# AdControl.net
KiCad netlist of a schematic drawn in Altium Designer
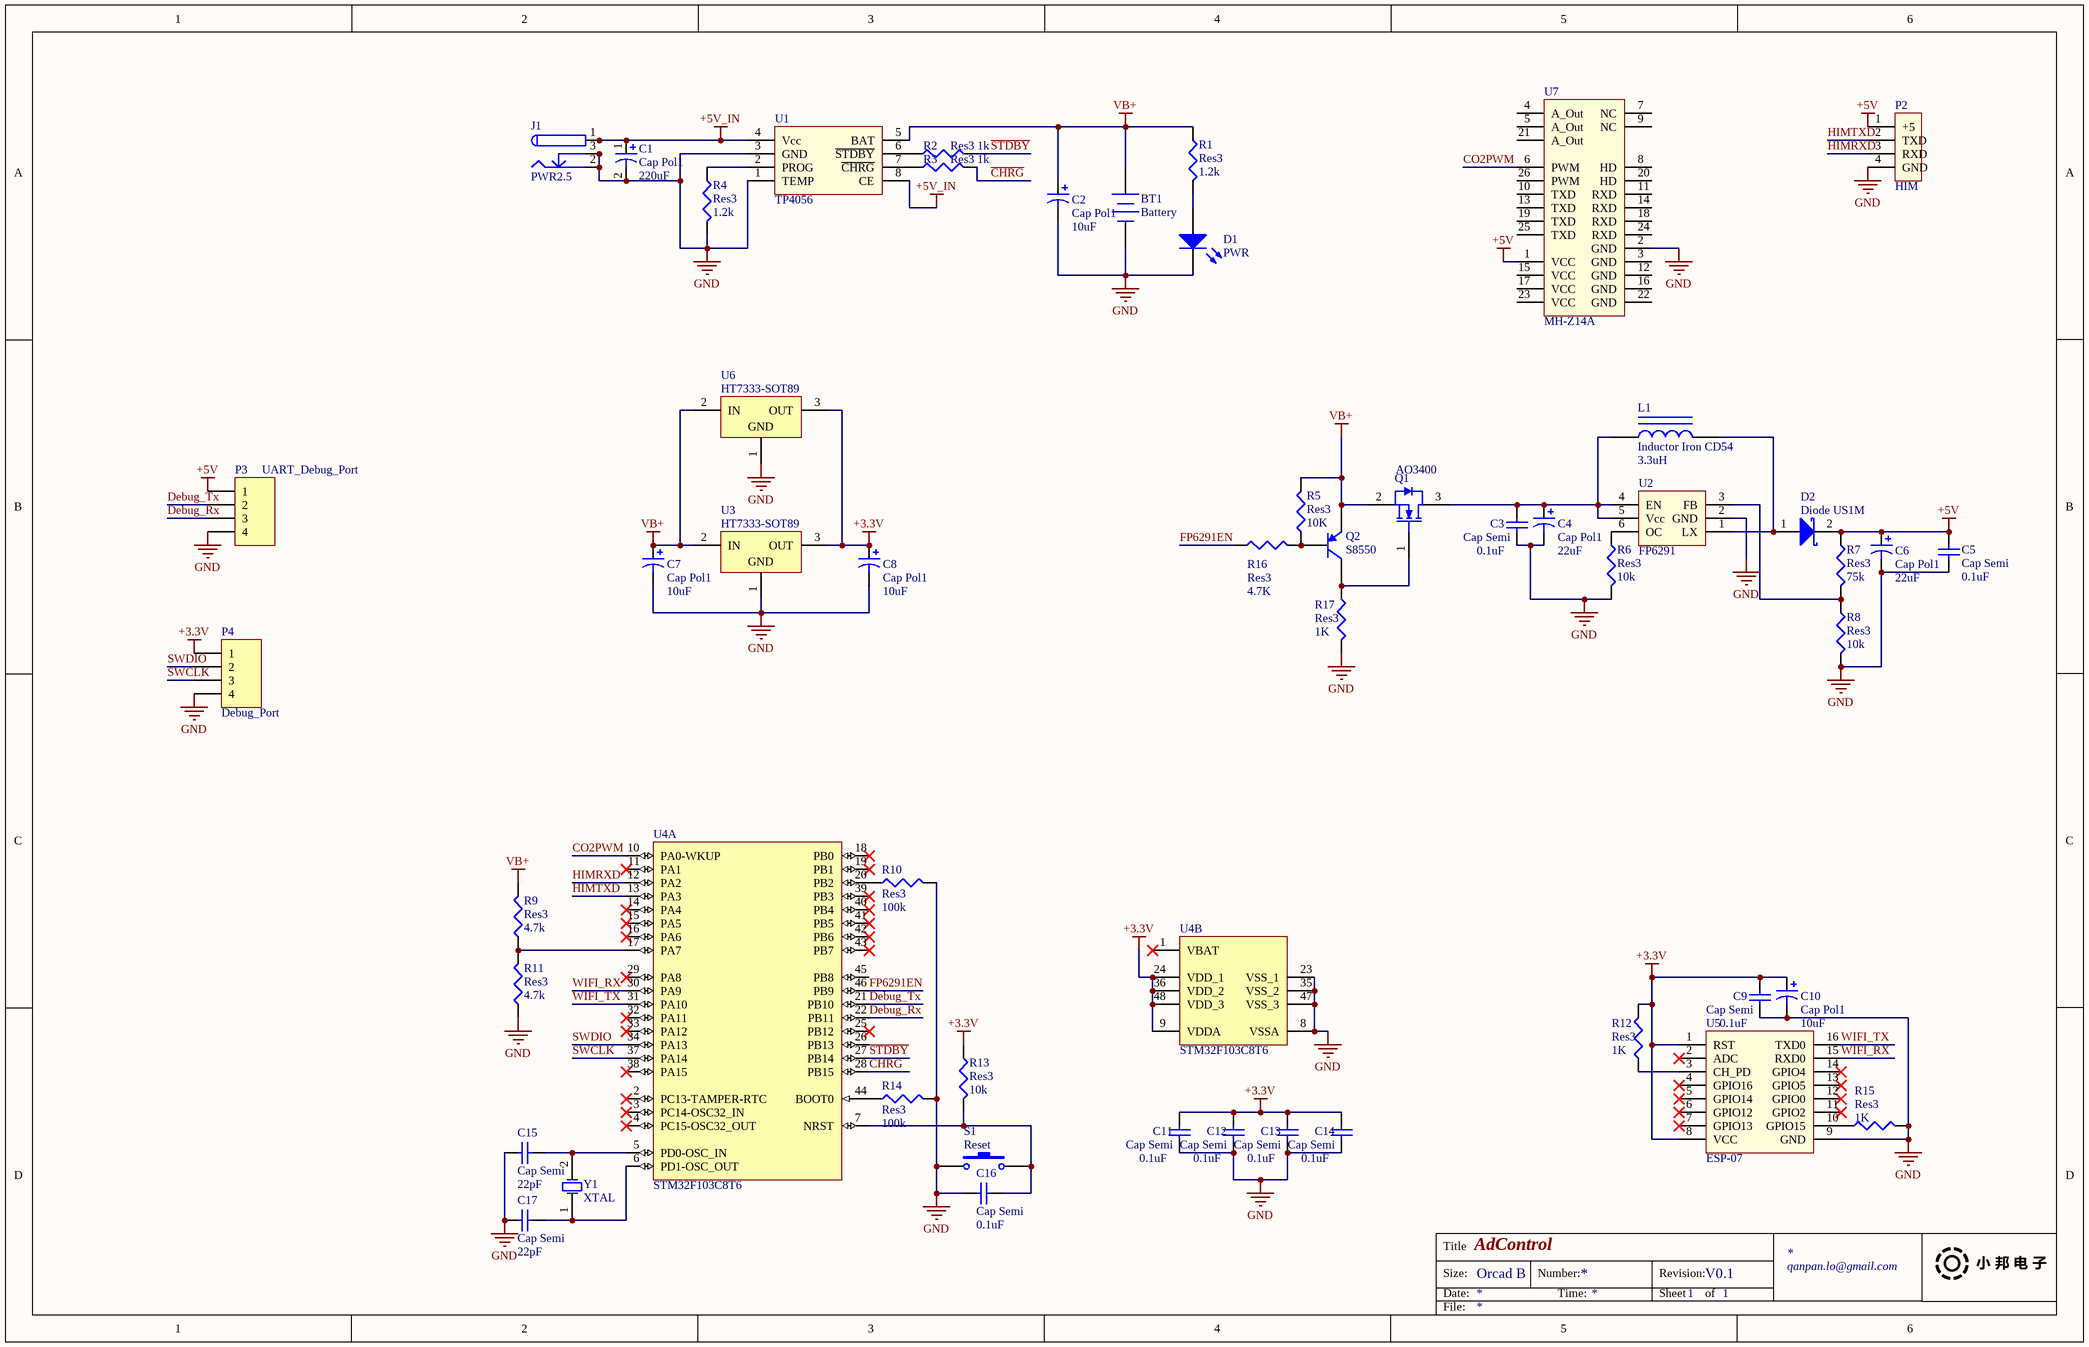
[diagram p0: AdControl.SchDoc]

(export (version "E")
  (design (tool "Eeschema 10.0.6"))
  (components
    (comp (ref "BT1")
      (value "Battery")
      (footprint "KF3.96_2P")
      (description "Multicell Battery")
      (fields (field (name "PUBLISHER") "Altium Limited"))
      (libsource (lib "Miscellaneous Devices") (part "Battery"))
    )
    (comp (ref "C1")
      (value "Cap Pol1")
      (footprint "CAP_6.3*5.4MM")
      (description "Polarized Capacitor (Radial)")
      (fields (field (name "ALTIUM_VALUE") "220uF") (field (name "PUBLISHER") "Altium Limited"))
      (libsource (lib "") (part "Cap Pol1_1"))
    )
    (comp (ref "C2")
      (value "Cap Pol1")
      (footprint "Cap_5*4mm")
      (description "Polarized Capacitor (Radial)")
      (fields (field (name "ALTIUM_VALUE") "10uF") (field (name "PUBLISHER") "Altium Limited"))
      (libsource (lib "Miscellaneous Devices") (part "Cap Pol1"))
    )
    (comp (ref "C3")
      (value "Cap Semi")
      (footprint "6-0805_N")
      (description "Capacitor (Semiconductor SIM Model)")
      (fields (field (name "ALTIUM_VALUE") "0.1uF") (field (name "PUBLISHER") "Altium Limited"))
      (libsource (lib "Miscellaneous Devices") (part "Cap Semi"))
    )
    (comp (ref "C4")
      (value "Cap Pol1")
      (footprint "Cap_5*4mm")
      (description "Polarized Capacitor (Radial)")
      (fields (field (name "ALTIUM_VALUE") "22uF") (field (name "PUBLISHER") "Altium Limited"))
      (libsource (lib "Miscellaneous Devices") (part "Cap Pol1"))
    )
    (comp (ref "C5")
      (value "Cap Semi")
      (footprint "6-0805_N")
      (description "Capacitor (Semiconductor SIM Model)")
      (fields (field (name "ALTIUM_VALUE") "0.1uF") (field (name "PUBLISHER") "Altium Limited"))
      (libsource (lib "Miscellaneous Devices") (part "Cap Semi"))
    )
    (comp (ref "C6")
      (value "Cap Pol1")
      (footprint "Cap_5*4mm")
      (description "Polarized Capacitor (Radial)")
      (fields (field (name "ALTIUM_VALUE") "22uF") (field (name "PUBLISHER") "Altium Limited"))
      (libsource (lib "Miscellaneous Devices") (part "Cap Pol1"))
    )
    (comp (ref "C7")
      (value "Cap Pol1")
      (footprint "Cap_5*4mm")
      (description "Polarized Capacitor (Radial)")
      (fields (field (name "ALTIUM_VALUE") "10uF") (field (name "PUBLISHER") "Altium Limited"))
      (libsource (lib "Miscellaneous Devices") (part "Cap Pol1"))
    )
    (comp (ref "C8")
      (value "Cap Pol1")
      (footprint "Cap_5*4mm")
      (description "Polarized Capacitor (Radial)")
      (fields (field (name "ALTIUM_VALUE") "10uF") (field (name "PUBLISHER") "Altium Limited"))
      (libsource (lib "Miscellaneous Devices") (part "Cap Pol1"))
    )
    (comp (ref "C9")
      (value "Cap Semi")
      (footprint "6-0805_N")
      (description "Capacitor (Semiconductor SIM Model)")
      (fields (field (name "ALTIUM_VALUE") "0.1uF") (field (name "PUBLISHER") "Altium Limited"))
      (libsource (lib "Miscellaneous Devices") (part "Cap Semi"))
    )
    (comp (ref "C10")
      (value "Cap Pol1")
      (footprint "Cap_5*4mm")
      (description "Polarized Capacitor (Radial)")
      (fields (field (name "ALTIUM_VALUE") "10uF") (field (name "PUBLISHER") "Altium Limited"))
      (libsource (lib "Miscellaneous Devices") (part "Cap Pol1"))
    )
    (comp (ref "C11")
      (value "Cap Semi")
      (footprint "6-0805_N")
      (description "Capacitor (Semiconductor SIM Model)")
      (fields (field (name "ALTIUM_VALUE") "0.1uF") (field (name "PUBLISHER") "Altium Limited"))
      (libsource (lib "Miscellaneous Devices") (part "Cap Semi"))
    )
    (comp (ref "C12")
      (value "Cap Semi")
      (footprint "6-0805_N")
      (description "Capacitor (Semiconductor SIM Model)")
      (fields (field (name "ALTIUM_VALUE") "0.1uF") (field (name "PUBLISHER") "Altium Limited"))
      (libsource (lib "Miscellaneous Devices") (part "Cap Semi"))
    )
    (comp (ref "C13")
      (value "Cap Semi")
      (footprint "6-0805_N")
      (description "Capacitor (Semiconductor SIM Model)")
      (fields (field (name "ALTIUM_VALUE") "0.1uF") (field (name "PUBLISHER") "Altium Limited"))
      (libsource (lib "Miscellaneous Devices") (part "Cap Semi"))
    )
    (comp (ref "C14")
      (value "Cap Semi")
      (footprint "6-0805_N")
      (description "Capacitor (Semiconductor SIM Model)")
      (fields (field (name "ALTIUM_VALUE") "0.1uF") (field (name "PUBLISHER") "Altium Limited"))
      (libsource (lib "Miscellaneous Devices") (part "Cap Semi"))
    )
    (comp (ref "C15")
      (value "Cap Semi")
      (footprint "6-0805_N")
      (description "Capacitor (Semiconductor SIM Model)")
      (fields (field (name "ALTIUM_VALUE") "22pF") (field (name "PUBLISHER") "Altium Limited"))
      (libsource (lib "Miscellaneous Devices") (part "Cap Semi"))
    )
    (comp (ref "C16")
      (value "Cap Semi")
      (footprint "6-0805_N")
      (description "Capacitor (Semiconductor SIM Model)")
      (fields (field (name "ALTIUM_VALUE") "0.1uF") (field (name "PUBLISHER") "Altium Limited"))
      (libsource (lib "Miscellaneous Devices") (part "Cap Semi"))
    )
    (comp (ref "C17")
      (value "Cap Semi")
      (footprint "6-0805_N")
      (description "Capacitor (Semiconductor SIM Model)")
      (fields (field (name "ALTIUM_VALUE") "22pF") (field (name "PUBLISHER") "Altium Limited"))
      (libsource (lib "Miscellaneous Devices") (part "Cap Semi"))
    )
    (comp (ref "D1")
      (value "PWR")
      (footprint "6-0805_N")
      (description "Typical INFRARED GaAs LED")
      (fields (field (name "PUBLISHER") "Altium Limited"))
      (libsource (lib "Miscellaneous Devices") (part "LED0"))
    )
    (comp (ref "D2")
      (value "Diode US1M")
      (footprint "US1M")
      (description "Silicon RF Schottky Diode for Mixer Applications in the VHF/UHF Range")
      (fields (field (name "PUBLISHER") "Altium Limited"))
      (libsource (lib "Miscellaneous Devices") (part "Diode BAT17"))
    )
    (comp (ref "J1")
      (value "PWR2.5")
      (footprint "KLD-3.5-1.3mm")
      (description "Low Voltage Power Supply Connector")
      (fields (field (name "PUBLISHER") "Altium Limited"))
      (libsource (lib "Miscellaneous Connectors") (part "PWR2.5"))
    )
    (comp (ref "L1")
      (value "Inductor Iron CD54")
      (footprint "CD54_Inductor")
      (description "Magnetic-Core Inductor")
      (fields (field (name "ALTIUM_VALUE") "3.3uH") (field (name "PUBLISHER") "Altium Limited"))
      (libsource (lib "Miscellaneous Devices") (part "Inductor Iron"))
    )
    (comp (ref "P2") (value "HIM") (footprint "XH2.54-4P") (libsource (lib "XH2.54") (part "XH2.54-4P")))
    (comp (ref "P3")
      (value "UART_Debug_Port")
      (footprint "HDR1X4")
      (description "Header, 4-Pin")
      (fields (field (name "PUBLISHER") "Altium Limited"))
      (libsource (lib "Miscellaneous Connectors") (part "Header 4"))
    )
    (comp (ref "P4")
      (value "Debug_Port")
      (footprint "HDR1X4")
      (description "Header, 4-Pin")
      (fields (field (name "PUBLISHER") "Altium Limited"))
      (libsource (lib "Miscellaneous Connectors") (part "Header 4"))
    )
    (comp (ref "Q1")
      (value "AO3400")
      (footprint "AO-SOT23-3_V")
      (description "N-channel Enhancement Mode Field-Effect Transistor; 5.8A/30V")
      (fields (field (name "MANUFACTURER") "Alpha and Omega"))
      (libsource (lib "Altium Content Vault") (part "AO-NEMOS-G1S2D3-3"))
    )
    (comp (ref "Q2")
      (value "S8550")
      (footprint "SOT-23B_L")
      (description "PNP Bipolar Transistor")
      (fields (field (name "PUBLISHER") "Altium Limited"))
      (libsource (lib "Miscellaneous Devices") (part "PNP"))
    )
    (comp (ref "R1")
      (value "Res3")
      (footprint "6-0805_N")
      (description "Resistor")
      (fields (field (name "ALTIUM_VALUE") "1.2k") (field (name "PUBLISHER") "Altium Limited"))
      (libsource (lib "Miscellaneous Devices") (part "Res3"))
    )
    (comp (ref "R2")
      (value "Res3")
      (footprint "6-0805_N")
      (description "Resistor")
      (fields (field (name "ALTIUM_VALUE") "1k") (field (name "PUBLISHER") "Altium Limited"))
      (libsource (lib "Miscellaneous Devices") (part "Res3"))
    )
    (comp (ref "R3")
      (value "Res3")
      (footprint "6-0805_N")
      (description "Resistor")
      (fields (field (name "ALTIUM_VALUE") "1k") (field (name "PUBLISHER") "Altium Limited"))
      (libsource (lib "Miscellaneous Devices") (part "Res3"))
    )
    (comp (ref "R4")
      (value "Res3")
      (footprint "6-0805_N")
      (description "Resistor")
      (fields (field (name "ALTIUM_VALUE") "1.2k") (field (name "PUBLISHER") "Altium Limited"))
      (libsource (lib "Miscellaneous Devices") (part "Res3"))
    )
    (comp (ref "R5")
      (value "Res3")
      (footprint "6-0805_N")
      (description "Resistor")
      (fields (field (name "ALTIUM_VALUE") "10K") (field (name "PUBLISHER") "Altium Limited"))
      (libsource (lib "Miscellaneous Devices") (part "Res3"))
    )
    (comp (ref "R6")
      (value "Res3")
      (footprint "6-0805_N")
      (description "Resistor")
      (fields (field (name "ALTIUM_VALUE") "10k") (field (name "PUBLISHER") "Altium Limited"))
      (libsource (lib "Miscellaneous Devices") (part "Res3"))
    )
    (comp (ref "R7")
      (value "Res3")
      (footprint "6-0805_N")
      (description "Resistor")
      (fields (field (name "ALTIUM_VALUE") "75k") (field (name "PUBLISHER") "Altium Limited"))
      (libsource (lib "Miscellaneous Devices") (part "Res3"))
    )
    (comp (ref "R8")
      (value "Res3")
      (footprint "6-0805_N")
      (description "Resistor")
      (fields (field (name "ALTIUM_VALUE") "10k") (field (name "PUBLISHER") "Altium Limited"))
      (libsource (lib "Miscellaneous Devices") (part "Res3"))
    )
    (comp (ref "R9")
      (value "Res3")
      (footprint "6-0805_N")
      (description "Resistor")
      (fields (field (name "ALTIUM_VALUE") "4.7k") (field (name "PUBLISHER") "Altium Limited"))
      (libsource (lib "Miscellaneous Devices") (part "Res3"))
    )
    (comp (ref "R10")
      (value "Res3")
      (footprint "6-0805_N")
      (description "Resistor")
      (fields (field (name "ALTIUM_VALUE") "100k") (field (name "PUBLISHER") "Altium Limited"))
      (libsource (lib "Miscellaneous Devices") (part "Res3"))
    )
    (comp (ref "R11")
      (value "Res3")
      (footprint "6-0805_N")
      (description "Resistor")
      (fields (field (name "ALTIUM_VALUE") "4.7k") (field (name "PUBLISHER") "Altium Limited"))
      (libsource (lib "Miscellaneous Devices") (part "Res3"))
    )
    (comp (ref "R12")
      (value "Res3")
      (footprint "6-0805_N")
      (description "Resistor")
      (fields (field (name "ALTIUM_VALUE") "1K") (field (name "PUBLISHER") "Altium Limited"))
      (libsource (lib "Miscellaneous Devices") (part "Res3"))
    )
    (comp (ref "R13")
      (value "Res3")
      (footprint "6-0805_N")
      (description "Resistor")
      (fields (field (name "ALTIUM_VALUE") "10k") (field (name "PUBLISHER") "Altium Limited"))
      (libsource (lib "Miscellaneous Devices") (part "Res3"))
    )
    (comp (ref "R14")
      (value "Res3")
      (footprint "6-0805_N")
      (description "Resistor")
      (fields (field (name "ALTIUM_VALUE") "100k") (field (name "PUBLISHER") "Altium Limited"))
      (libsource (lib "Miscellaneous Devices") (part "Res3"))
    )
    (comp (ref "R15")
      (value "Res3")
      (footprint "6-0805_N")
      (description "Resistor")
      (fields (field (name "ALTIUM_VALUE") "1K") (field (name "PUBLISHER") "Altium Limited"))
      (libsource (lib "Miscellaneous Devices") (part "Res3"))
    )
    (comp (ref "R16")
      (value "Res3")
      (footprint "6-0805_N")
      (description "Resistor")
      (fields (field (name "ALTIUM_VALUE") "4.7K") (field (name "PUBLISHER") "Altium Limited"))
      (libsource (lib "Miscellaneous Devices") (part "Res3"))
    )
    (comp (ref "R17")
      (value "Res3")
      (footprint "6-0805_N")
      (description "Resistor")
      (fields (field (name "ALTIUM_VALUE") "1K") (field (name "PUBLISHER") "Altium Limited"))
      (libsource (lib "Miscellaneous Devices") (part "Res3"))
    )
    (comp (ref "S1")
      (value "Reset")
      (footprint "SWP_PB_6.5mm")
      (description "Switch")
      (fields (field (name "PUBLISHER") "Altium Limited"))
      (libsource (lib "Miscellaneous Devices") (part "SW-PB"))
    )
    (comp (ref "U1")
      (value "TP4056")
      (footprint "Power_SOP8")
      (libsource (lib "Simon'Library") (part "TP4056"))
    )
    (comp (ref "U2")
      (value "FP6291")
      (footprint "SOT23-6L")
      (libsource (lib "Simon'Library") (part "FP6291"))
    )
    (comp (ref "U3")
      (value "HT7333-SOT89")
      (footprint "SOT89_N")
      (description "Low Power Consumption LDO, Output Voltage 3.3V, SOT89 Pkg")
      (libsource (lib "Altium Content Vault") (part "PM-REG-HT73XX-IL3"))
    )
    (comp (ref "U4")
      (value "STM32F103C8T6")
      (footprint "STM-LQFP48_L")
      (libsource (lib "Altium Content Vault") (part "MC-ARM-STM32F103X8_B-SQ48"))
    )
    (comp (ref "U5")
      (value "ESP-07")
      (footprint "ESP-07_Wifi")
      (libsource (lib "Simon'Library") (part "ESP-07_Wifi"))
    )
    (comp (ref "U6")
      (value "HT7333-SOT89")
      (footprint "SOT89_N")
      (description "Low Power Consumption LDO, Output Voltage 3.3V, SOT89 Pkg")
      (libsource (lib "Altium Content Vault") (part "PM-REG-HT73XX-IL3"))
    )
    (comp (ref "U7")
      (value "MH-Z14A")
      (footprint "MH-Z14A")
      (description "CO2 Detector")
      (libsource (lib "Simon'Library") (part "MH-Z14A"))
    )
    (comp (ref "Y1")
      (value "XTAL")
      (footprint "OSC_5032_2Pin")
      (description "Crystal Oscillator")
      (fields (field (name "PUBLISHER") "Altium Limited"))
      (libsource (lib "Miscellaneous Devices") (part "XTAL"))
    )
  )
  (nets
    (net (code "1") (name "+3.3V") (class "Default")
      (node (ref "C10") (pin "1") (pinfunction "1_1") (pintype "passive"))
      (node (ref "C11") (pin "1") (pinfunction "1_1") (pintype "passive"))
      (node (ref "C12") (pin "1") (pinfunction "1_1") (pintype "passive"))
      (node (ref "C13") (pin "1") (pinfunction "1_1") (pintype "passive"))
      (node (ref "C14") (pin "1") (pinfunction "1_1") (pintype "passive"))
      (node (ref "C8") (pin "1") (pinfunction "1_1") (pintype "passive"))
      (node (ref "C9") (pin "1") (pinfunction "1_1") (pintype "passive"))
      (node (ref "P4") (pin "1") (pinfunction "1_1") (pintype "passive"))
      (node (ref "R12") (pin "2") (pinfunction "2_2") (pintype "passive"))
      (node (ref "R13") (pin "1") (pinfunction "1_1") (pintype "passive"))
      (node (ref "U3") (pin "3") (pinfunction "OUT_3") (pintype "power_in"))
      (node (ref "U4") (pin "24") (pinfunction "VDD_1_24") (pintype "power_in"))
      (node (ref "U4") (pin "36") (pinfunction "VDD_2_36") (pintype "power_in"))
      (node (ref "U4") (pin "48") (pinfunction "VDD_3_48") (pintype "power_in"))
      (node (ref "U4") (pin "9") (pinfunction "VDDA_9") (pintype "power_in"))
      (node (ref "U5") (pin "1") (pinfunction "RST_1") (pintype "passive"))
      (node (ref "U5") (pin "8") (pinfunction "VCC_8") (pintype "passive"))
      (node (ref "U6") (pin "3") (pinfunction "OUT_3") (pintype "power_in"))
    )
    (net (code "2") (name "+5V") (class "Default")
      (node (ref "C5") (pin "1") (pinfunction "1_1") (pintype "passive"))
      (node (ref "C6") (pin "1") (pinfunction "1_1") (pintype "passive"))
      (node (ref "D2") (pin "2") (pinfunction "K_2") (pintype "passive"))
      (node (ref "P2") (pin "1") (pinfunction "+5_1") (pintype "passive"))
      (node (ref "P3") (pin "1") (pinfunction "1_1") (pintype "passive"))
      (node (ref "R7") (pin "1") (pinfunction "1_1") (pintype "passive"))
      (node (ref "U7") (pin "1") (pinfunction "VCC_1") (pintype "passive"))
    )
    (net (code "3") (name "+5V_IN") (class "Default")
      (node (ref "C1") (pin "1") (pinfunction "1_1") (pintype "passive"))
      (node (ref "J1") (pin "1") (pinfunction "1_1") (pintype "power_in"))
      (node (ref "J1") (pin "1A") (pinfunction "1A_1A") (pintype "power_in"))
      (node (ref "J1") (pin "1B") (pinfunction "1B_1B") (pintype "power_in"))
      (node (ref "U1") (pin "4") (pinfunction "Vcc_4") (pintype "passive"))
      (node (ref "U1") (pin "8") (pinfunction "CE_8") (pintype "passive"))
    )
    (net (code "4") (name "/CO2PWM") (class "Default")
      (node (ref "U4") (pin "10") (pinfunction "PA0-WKUP_10") (pintype "bidirectional"))
      (node (ref "U7") (pin "6") (pinfunction "PWM_6") (pintype "passive"))
    )
    (net (code "5") (name "/Debug_Rx") (class "Default")
      (node (ref "P3") (pin "3") (pinfunction "3_3") (pintype "passive"))
      (node (ref "U4") (pin "22") (pinfunction "PB11_22") (pintype "bidirectional"))
    )
    (net (code "6") (name "/Debug_Tx") (class "Default")
      (node (ref "P3") (pin "2") (pinfunction "2_2") (pintype "passive"))
      (node (ref "U4") (pin "21") (pinfunction "PB10_21") (pintype "bidirectional"))
    )
    (net (code "7") (name "/FP6291EN") (class "Default")
      (node (ref "R16") (pin "1") (pinfunction "1_1") (pintype "passive"))
      (node (ref "U4") (pin "46") (pinfunction "PB9_46") (pintype "bidirectional"))
    )
    (net (code "8") (name "/HIMRXD") (class "Default")
      (node (ref "P2") (pin "3") (pinfunction "RXD_3") (pintype "passive"))
      (node (ref "U4") (pin "12") (pinfunction "PA2_12") (pintype "bidirectional"))
    )
    (net (code "9") (name "/HIMTXD") (class "Default")
      (node (ref "P2") (pin "2") (pinfunction "TXD_2") (pintype "passive"))
      (node (ref "U4") (pin "13") (pinfunction "PA3_13") (pintype "bidirectional"))
    )
    (net (code "10") (name "/SWCLK") (class "Default")
      (node (ref "P4") (pin "3") (pinfunction "3_3") (pintype "passive"))
      (node (ref "U4") (pin "37") (pinfunction "PA14_37") (pintype "bidirectional"))
    )
    (net (code "11") (name "/SWDIO") (class "Default")
      (node (ref "P4") (pin "2") (pinfunction "2_2") (pintype "passive"))
      (node (ref "U4") (pin "34") (pinfunction "PA13_34") (pintype "bidirectional"))
    )
    (net (code "12") (name "/WIFI_RX") (class "Default")
      (node (ref "U4") (pin "30") (pinfunction "PA9_30") (pintype "bidirectional"))
      (node (ref "U5") (pin "15") (pinfunction "RXD0_15") (pintype "passive"))
    )
    (net (code "13") (name "/WIFI_TX") (class "Default")
      (node (ref "U4") (pin "31") (pinfunction "PA10_31") (pintype "bidirectional"))
      (node (ref "U5") (pin "16") (pinfunction "TXD0_16") (pintype "passive"))
    )
    (net (code "14") (name "/~{CHRG}") (class "Default")
      (node (ref "R3") (pin "2") (pinfunction "2_2") (pintype "passive"))
      (node (ref "U4") (pin "28") (pinfunction "PB15_28") (pintype "bidirectional"))
    )
    (net (code "15") (name "/~{STDBY}") (class "Default")
      (node (ref "R2") (pin "2") (pinfunction "2_2") (pintype "passive"))
      (node (ref "U4") (pin "27") (pinfunction "PB14_27") (pintype "bidirectional"))
    )
    (net (code "16") (name "GND") (class "Default")
      (node (ref "BT1") (pin "2") (pinfunction "-_2") (pintype "passive"))
      (node (ref "C1") (pin "2") (pinfunction "2_2") (pintype "passive"))
      (node (ref "C10") (pin "2") (pinfunction "2_2") (pintype "passive"))
      (node (ref "C11") (pin "2") (pinfunction "2_2") (pintype "passive"))
      (node (ref "C12") (pin "2") (pinfunction "2_2") (pintype "passive"))
      (node (ref "C13") (pin "2") (pinfunction "2_2") (pintype "passive"))
      (node (ref "C14") (pin "2") (pinfunction "2_2") (pintype "passive"))
      (node (ref "C15") (pin "2") (pinfunction "2_2") (pintype "passive"))
      (node (ref "C16") (pin "1") (pinfunction "1_1") (pintype "passive"))
      (node (ref "C17") (pin "2") (pinfunction "2_2") (pintype "passive"))
      (node (ref "C2") (pin "2") (pinfunction "2_2") (pintype "passive"))
      (node (ref "C3") (pin "2") (pinfunction "2_2") (pintype "passive"))
      (node (ref "C4") (pin "2") (pinfunction "2_2") (pintype "passive"))
      (node (ref "C5") (pin "2") (pinfunction "2_2") (pintype "passive"))
      (node (ref "C6") (pin "2") (pinfunction "2_2") (pintype "passive"))
      (node (ref "C7") (pin "2") (pinfunction "2_2") (pintype "passive"))
      (node (ref "C8") (pin "2") (pinfunction "2_2") (pintype "passive"))
      (node (ref "C9") (pin "2") (pinfunction "2_2") (pintype "passive"))
      (node (ref "D1") (pin "2") (pinfunction "K_2") (pintype "passive"))
      (node (ref "J1") (pin "2") (pinfunction "2_2") (pintype "power_in"))
      (node (ref "J1") (pin "2A") (pinfunction "2A_2A") (pintype "power_in"))
      (node (ref "J1") (pin "2B") (pinfunction "2B_2B") (pintype "power_in"))
      (node (ref "J1") (pin "3") (pinfunction "3_3") (pintype "power_in"))
      (node (ref "J1") (pin "3A") (pinfunction "3A_3A") (pintype "power_in"))
      (node (ref "J1") (pin "3B") (pinfunction "3B_3B") (pintype "power_in"))
      (node (ref "P2") (pin "4") (pinfunction "GND_4") (pintype "passive"))
      (node (ref "P3") (pin "4") (pinfunction "4_4") (pintype "passive"))
      (node (ref "P4") (pin "4") (pinfunction "4_4") (pintype "passive"))
      (node (ref "R10") (pin "2") (pinfunction "2_2") (pintype "passive"))
      (node (ref "R11") (pin "2") (pinfunction "2_2") (pintype "passive"))
      (node (ref "R14") (pin "2") (pinfunction "2_2") (pintype "passive"))
      (node (ref "R15") (pin "2") (pinfunction "2_2") (pintype "passive"))
      (node (ref "R17") (pin "2") (pinfunction "2_2") (pintype "passive"))
      (node (ref "R4") (pin "2") (pinfunction "2_2") (pintype "passive"))
      (node (ref "R6") (pin "2") (pinfunction "2_2") (pintype "passive"))
      (node (ref "R8") (pin "2") (pinfunction "2_2") (pintype "passive"))
      (node (ref "S1") (pin "1") (pinfunction "1_1") (pintype "passive"))
      (node (ref "U1") (pin "1") (pinfunction "TEMP_1") (pintype "passive"))
      (node (ref "U1") (pin "3") (pinfunction "GND_3") (pintype "passive"))
      (node (ref "U2") (pin "2") (pinfunction "GND_2") (pintype "passive"))
      (node (ref "U3") (pin "1") (pinfunction "GND_1") (pintype "power_in"))
      (node (ref "U4") (pin "23") (pinfunction "VSS_1_23") (pintype "power_in"))
      (node (ref "U4") (pin "35") (pinfunction "VSS_2_35") (pintype "power_in"))
      (node (ref "U4") (pin "47") (pinfunction "VSS_3_47") (pintype "power_in"))
      (node (ref "U4") (pin "8") (pinfunction "VSSA_8") (pintype "power_in"))
      (node (ref "U5") (pin "9") (pinfunction "GND_9") (pintype "passive"))
      (node (ref "U6") (pin "1") (pinfunction "GND_1") (pintype "power_in"))
      (node (ref "U7") (pin "2") (pinfunction "GND_2") (pintype "passive"))
    )
    (net (code "17") (name "Net-(D1-A)") (class "Default")
      (node (ref "D1") (pin "1") (pinfunction "A_1") (pintype "passive"))
      (node (ref "R1") (pin "2") (pinfunction "2_2") (pintype "passive"))
    )
    (net (code "18") (name "Net-(D2-A)") (class "Default")
      (node (ref "D2") (pin "1") (pinfunction "A_1") (pintype "passive"))
      (node (ref "L1") (pin "2") (pinfunction "2_2") (pintype "passive"))
      (node (ref "U2") (pin "1") (pinfunction "LX_1") (pintype "passive"))
    )
    (net (code "19") (name "Net-(Q1-D)") (class "Default")
      (node (ref "C3") (pin "1") (pinfunction "1_1") (pintype "passive"))
      (node (ref "C4") (pin "1") (pinfunction "1_1") (pintype "passive"))
      (node (ref "L1") (pin "1") (pinfunction "1_1") (pintype "passive"))
      (node (ref "Q1") (pin "3") (pinfunction "D_3") (pintype "passive"))
      (node (ref "U2") (pin "4") (pinfunction "EN_4") (pintype "passive"))
      (node (ref "U2") (pin "5") (pinfunction "Vcc_5") (pintype "passive"))
    )
    (net (code "20") (name "Net-(Q1-G)") (class "Default")
      (node (ref "Q1") (pin "1") (pinfunction "G_1") (pintype "passive"))
      (node (ref "Q2") (pin "1") (pinfunction "C_1") (pintype "passive"))
      (node (ref "R17") (pin "1") (pinfunction "1_1") (pintype "passive"))
    )
    (net (code "21") (name "Net-(Q2-B)") (class "Default")
      (node (ref "Q2") (pin "2") (pinfunction "B_2") (pintype "passive"))
      (node (ref "R16") (pin "2") (pinfunction "2_2") (pintype "passive"))
      (node (ref "R5") (pin "1") (pinfunction "1_1") (pintype "passive"))
    )
    (net (code "22") (name "Net-(U1-PROG)") (class "Default")
      (node (ref "R4") (pin "1") (pinfunction "1_1") (pintype "passive"))
      (node (ref "U1") (pin "2") (pinfunction "PROG_2") (pintype "passive"))
    )
    (net (code "23") (name "Net-(U1-~{CHRG})") (class "Default")
      (node (ref "R3") (pin "1") (pinfunction "1_1") (pintype "passive"))
      (node (ref "U1") (pin "7") (pinfunction "~{CHRG}_7") (pintype "passive"))
    )
    (net (code "24") (name "Net-(U1-~{STDBY})") (class "Default")
      (node (ref "R2") (pin "1") (pinfunction "1_1") (pintype "passive"))
      (node (ref "U1") (pin "6") (pinfunction "~{STDBY}_6") (pintype "passive"))
    )
    (net (code "25") (name "Net-(U2-FB)") (class "Default")
      (node (ref "R7") (pin "2") (pinfunction "2_2") (pintype "passive"))
      (node (ref "R8") (pin "1") (pinfunction "1_1") (pintype "passive"))
      (node (ref "U2") (pin "3") (pinfunction "FB_3") (pintype "passive"))
    )
    (net (code "26") (name "Net-(U2-OC)") (class "Default")
      (node (ref "R6") (pin "1") (pinfunction "1_1") (pintype "passive"))
      (node (ref "U2") (pin "6") (pinfunction "OC_6") (pintype "passive"))
    )
    (net (code "27") (name "Net-(U4A-BOOT0)") (class "Default")
      (node (ref "R14") (pin "1") (pinfunction "1_1") (pintype "passive"))
      (node (ref "U4") (pin "44") (pinfunction "BOOT0_44") (pintype "input"))
    )
    (net (code "28") (name "Net-(U4A-NRST)") (class "Default")
      (node (ref "C16") (pin "2") (pinfunction "2_2") (pintype "passive"))
      (node (ref "R13") (pin "2") (pinfunction "2_2") (pintype "passive"))
      (node (ref "S1") (pin "2") (pinfunction "2_2") (pintype "passive"))
      (node (ref "U4") (pin "7") (pinfunction "NRST_7") (pintype "bidirectional"))
    )
    (net (code "29") (name "Net-(U4A-PA7)") (class "Default")
      (node (ref "R11") (pin "1") (pinfunction "1_1") (pintype "passive"))
      (node (ref "R9") (pin "2") (pinfunction "2_2") (pintype "passive"))
      (node (ref "U4") (pin "17") (pinfunction "PA7_17") (pintype "bidirectional"))
    )
    (net (code "30") (name "Net-(U4A-PB2)") (class "Default")
      (node (ref "R10") (pin "1") (pinfunction "1_1") (pintype "passive"))
      (node (ref "U4") (pin "20") (pinfunction "PB2_20") (pintype "bidirectional"))
    )
    (net (code "31") (name "Net-(U4A-PD0-OSC_IN)") (class "Default")
      (node (ref "C15") (pin "1") (pinfunction "1_1") (pintype "passive"))
      (node (ref "U4") (pin "5") (pinfunction "PD0-OSC_IN_5") (pintype "bidirectional"))
      (node (ref "Y1") (pin "2") (pinfunction "OSC2_2") (pintype "passive"))
    )
    (net (code "32") (name "Net-(U4A-PD1-OSC_OUT)") (class "Default")
      (node (ref "C17") (pin "1") (pinfunction "1_1") (pintype "passive"))
      (node (ref "U4") (pin "6") (pinfunction "PD1-OSC_OUT_6") (pintype "bidirectional"))
      (node (ref "Y1") (pin "1") (pinfunction "OSC1_1") (pintype "passive"))
    )
    (net (code "33") (name "Net-(U5-CH_PD)") (class "Default")
      (node (ref "R12") (pin "1") (pinfunction "1_1") (pintype "passive"))
      (node (ref "U5") (pin "3") (pinfunction "CH_PD_3") (pintype "passive"))
    )
    (net (code "34") (name "Net-(U5-GPIO15)") (class "Default")
      (node (ref "R15") (pin "1") (pinfunction "1_1") (pintype "passive"))
      (node (ref "U5") (pin "10") (pinfunction "GPIO15_10") (pintype "passive"))
    )
    (net (code "35") (name "VB+") (class "Default")
      (node (ref "BT1") (pin "1") (pinfunction "+_1") (pintype "passive"))
      (node (ref "C2") (pin "1") (pinfunction "1_1") (pintype "passive"))
      (node (ref "C7") (pin "1") (pinfunction "1_1") (pintype "passive"))
      (node (ref "Q1") (pin "2") (pinfunction "S_2") (pintype "passive"))
      (node (ref "Q2") (pin "3") (pinfunction "E_3") (pintype "passive"))
      (node (ref "R1") (pin "1") (pinfunction "1_1") (pintype "passive"))
      (node (ref "R5") (pin "2") (pinfunction "2_2") (pintype "passive"))
      (node (ref "R9") (pin "1") (pinfunction "1_1") (pintype "passive"))
      (node (ref "U1") (pin "5") (pinfunction "BAT_5") (pintype "passive"))
      (node (ref "U3") (pin "2") (pinfunction "IN_2") (pintype "power_in"))
      (node (ref "U6") (pin "2") (pinfunction "IN_2") (pintype "power_in"))
    )
    (net (code "36") (name "unconnected-(U4A-PA1-Pad11)") (class "Default")
      (node (ref "U4") (pin "11") (pinfunction "PA1_11") (pintype "bidirectional+no_connect"))
    )
    (net (code "37") (name "unconnected-(U4A-PA4-Pad14)") (class "Default")
      (node (ref "U4") (pin "14") (pinfunction "PA4_14") (pintype "bidirectional+no_connect"))
    )
    (net (code "38") (name "unconnected-(U4A-PA5-Pad15)") (class "Default")
      (node (ref "U4") (pin "15") (pinfunction "PA5_15") (pintype "bidirectional+no_connect"))
    )
    (net (code "39") (name "unconnected-(U4A-PA6-Pad16)") (class "Default")
      (node (ref "U4") (pin "16") (pinfunction "PA6_16") (pintype "bidirectional+no_connect"))
    )
    (net (code "40") (name "unconnected-(U4A-PA8-Pad29)") (class "Default")
      (node (ref "U4") (pin "29") (pinfunction "PA8_29") (pintype "bidirectional+no_connect"))
    )
    (net (code "41") (name "unconnected-(U4A-PA11-Pad32)") (class "Default")
      (node (ref "U4") (pin "32") (pinfunction "PA11_32") (pintype "bidirectional+no_connect"))
    )
    (net (code "42") (name "unconnected-(U4A-PA12-Pad33)") (class "Default")
      (node (ref "U4") (pin "33") (pinfunction "PA12_33") (pintype "bidirectional+no_connect"))
    )
    (net (code "43") (name "unconnected-(U4A-PA15-Pad38)") (class "Default")
      (node (ref "U4") (pin "38") (pinfunction "PA15_38") (pintype "bidirectional+no_connect"))
    )
    (net (code "44") (name "unconnected-(U4A-PB0-Pad18)") (class "Default")
      (node (ref "U4") (pin "18") (pinfunction "PB0_18") (pintype "bidirectional+no_connect"))
    )
    (net (code "45") (name "unconnected-(U4A-PB1-Pad19)") (class "Default")
      (node (ref "U4") (pin "19") (pinfunction "PB1_19") (pintype "bidirectional+no_connect"))
    )
    (net (code "46") (name "unconnected-(U4A-PB3-Pad39)") (class "Default")
      (node (ref "U4") (pin "39") (pinfunction "PB3_39") (pintype "bidirectional+no_connect"))
    )
    (net (code "47") (name "unconnected-(U4A-PB4-Pad40)") (class "Default")
      (node (ref "U4") (pin "40") (pinfunction "PB4_40") (pintype "bidirectional+no_connect"))
    )
    (net (code "48") (name "unconnected-(U4A-PB5-Pad41)") (class "Default")
      (node (ref "U4") (pin "41") (pinfunction "PB5_41") (pintype "bidirectional+no_connect"))
    )
    (net (code "49") (name "unconnected-(U4A-PB6-Pad42)") (class "Default")
      (node (ref "U4") (pin "42") (pinfunction "PB6_42") (pintype "bidirectional+no_connect"))
    )
    (net (code "50") (name "unconnected-(U4A-PB7-Pad43)") (class "Default")
      (node (ref "U4") (pin "43") (pinfunction "PB7_43") (pintype "bidirectional+no_connect"))
    )
    (net (code "51") (name "unconnected-(U4A-PB8-Pad45)") (class "Default")
      (node (ref "U4") (pin "45") (pinfunction "PB8_45") (pintype "bidirectional"))
    )
    (net (code "52") (name "unconnected-(U4A-PB12-Pad25)") (class "Default")
      (node (ref "U4") (pin "25") (pinfunction "PB12_25") (pintype "bidirectional+no_connect"))
    )
    (net (code "53") (name "unconnected-(U4A-PB13-Pad26)") (class "Default")
      (node (ref "U4") (pin "26") (pinfunction "PB13_26") (pintype "bidirectional"))
    )
    (net (code "54") (name "unconnected-(U4A-PC13-TAMPER-RTC-Pad2)") (class "Default")
      (node (ref "U4") (pin "2") (pinfunction "PC13-TAMPER-RTC_2") (pintype "bidirectional+no_connect"))
    )
    (net (code "55") (name "unconnected-(U4A-PC14-OSC32_IN-Pad3)") (class "Default")
      (node (ref "U4") (pin "3") (pinfunction "PC14-OSC32_IN_3") (pintype "bidirectional+no_connect"))
    )
    (net (code "56") (name "unconnected-(U4A-PC15-OSC32_OUT-Pad4)") (class "Default")
      (node (ref "U4") (pin "4") (pinfunction "PC15-OSC32_OUT_4") (pintype "bidirectional+no_connect"))
    )
    (net (code "57") (name "unconnected-(U4B-VBAT-Pad1)") (class "Default")
      (node (ref "U4") (pin "1") (pinfunction "VBAT_1") (pintype "power_in+no_connect"))
    )
    (net (code "58") (name "unconnected-(U5-ADC-Pad2)") (class "Default")
      (node (ref "U5") (pin "2") (pinfunction "ADC_2") (pintype "passive+no_connect"))
    )
    (net (code "59") (name "unconnected-(U5-GPIO0-Pad12)") (class "Default")
      (node (ref "U5") (pin "12") (pinfunction "GPIO0_12") (pintype "passive+no_connect"))
    )
    (net (code "60") (name "unconnected-(U5-GPIO2-Pad11)") (class "Default")
      (node (ref "U5") (pin "11") (pinfunction "GPIO2_11") (pintype "passive+no_connect"))
    )
    (net (code "61") (name "unconnected-(U5-GPIO4-Pad14)") (class "Default")
      (node (ref "U5") (pin "14") (pinfunction "GPIO4_14") (pintype "passive+no_connect"))
    )
    (net (code "62") (name "unconnected-(U5-GPIO5-Pad13)") (class "Default")
      (node (ref "U5") (pin "13") (pinfunction "GPIO5_13") (pintype "passive+no_connect"))
    )
    (net (code "63") (name "unconnected-(U5-GPIO12-Pad6)") (class "Default")
      (node (ref "U5") (pin "6") (pinfunction "GPIO12_6") (pintype "passive+no_connect"))
    )
    (net (code "64") (name "unconnected-(U5-GPIO13-Pad7)") (class "Default")
      (node (ref "U5") (pin "7") (pinfunction "GPIO13_7") (pintype "passive+no_connect"))
    )
    (net (code "65") (name "unconnected-(U5-GPIO14-Pad5)") (class "Default")
      (node (ref "U5") (pin "5") (pinfunction "GPIO14_5") (pintype "passive+no_connect"))
    )
    (net (code "66") (name "unconnected-(U5-GPIO16-Pad4)") (class "Default")
      (node (ref "U5") (pin "4") (pinfunction "GPIO16_4") (pintype "passive+no_connect"))
    )
    (net (code "67") (name "unconnected-(U7-A_Out-Pad4)") (class "Default")
      (node (ref "U7") (pin "4") (pinfunction "A_Out_4") (pintype "passive"))
    )
    (net (code "68") (name "unconnected-(U7-A_Out-Pad5)") (class "Default")
      (node (ref "U7") (pin "5") (pinfunction "A_Out_5") (pintype "passive"))
    )
    (net (code "69") (name "unconnected-(U7-A_Out-Pad21)") (class "Default")
      (node (ref "U7") (pin "21") (pinfunction "A_Out_21") (pintype "passive"))
    )
    (net (code "70") (name "unconnected-(U7-GND-Pad3)") (class "Default")
      (node (ref "U7") (pin "3") (pinfunction "GND_3") (pintype "passive"))
    )
    (net (code "71") (name "unconnected-(U7-GND-Pad12)") (class "Default")
      (node (ref "U7") (pin "12") (pinfunction "GND_12") (pintype "passive"))
    )
    (net (code "72") (name "unconnected-(U7-GND-Pad16)") (class "Default")
      (node (ref "U7") (pin "16") (pinfunction "GND_16") (pintype "passive"))
    )
    (net (code "73") (name "unconnected-(U7-GND-Pad22)") (class "Default")
      (node (ref "U7") (pin "22") (pinfunction "GND_22") (pintype "passive"))
    )
    (net (code "74") (name "unconnected-(U7-HD-Pad8)") (class "Default")
      (node (ref "U7") (pin "8") (pinfunction "HD_8") (pintype "passive"))
    )
    (net (code "75") (name "unconnected-(U7-HD-Pad20)") (class "Default")
      (node (ref "U7") (pin "20") (pinfunction "HD_20") (pintype "passive"))
    )
    (net (code "76") (name "unconnected-(U7-NC-Pad7)") (class "Default")
      (node (ref "U7") (pin "7") (pinfunction "NC_7") (pintype "passive"))
    )
    (net (code "77") (name "unconnected-(U7-NC-Pad9)") (class "Default")
      (node (ref "U7") (pin "9") (pinfunction "NC_9") (pintype "passive"))
    )
    (net (code "78") (name "unconnected-(U7-PWM-Pad26)") (class "Default")
      (node (ref "U7") (pin "26") (pinfunction "PWM_26") (pintype "passive"))
    )
    (net (code "79") (name "unconnected-(U7-RXD-Pad11)") (class "Default")
      (node (ref "U7") (pin "11") (pinfunction "RXD_11") (pintype "passive"))
    )
    (net (code "80") (name "unconnected-(U7-RXD-Pad14)") (class "Default")
      (node (ref "U7") (pin "14") (pinfunction "RXD_14") (pintype "passive"))
    )
    (net (code "81") (name "unconnected-(U7-RXD-Pad18)") (class "Default")
      (node (ref "U7") (pin "18") (pinfunction "RXD_18") (pintype "passive"))
    )
    (net (code "82") (name "unconnected-(U7-RXD-Pad24)") (class "Default")
      (node (ref "U7") (pin "24") (pinfunction "RXD_24") (pintype "passive"))
    )
    (net (code "83") (name "unconnected-(U7-TXD-Pad10)") (class "Default")
      (node (ref "U7") (pin "10") (pinfunction "TXD_10") (pintype "passive"))
    )
    (net (code "84") (name "unconnected-(U7-TXD-Pad13)") (class "Default")
      (node (ref "U7") (pin "13") (pinfunction "TXD_13") (pintype "passive"))
    )
    (net (code "85") (name "unconnected-(U7-TXD-Pad19)") (class "Default")
      (node (ref "U7") (pin "19") (pinfunction "TXD_19") (pintype "passive"))
    )
    (net (code "86") (name "unconnected-(U7-TXD-Pad25)") (class "Default")
      (node (ref "U7") (pin "25") (pinfunction "TXD_25") (pintype "passive"))
    )
    (net (code "87") (name "unconnected-(U7-VCC-Pad15)") (class "Default")
      (node (ref "U7") (pin "15") (pinfunction "VCC_15") (pintype "passive"))
    )
    (net (code "88") (name "unconnected-(U7-VCC-Pad17)") (class "Default")
      (node (ref "U7") (pin "17") (pinfunction "VCC_17") (pintype "passive"))
    )
    (net (code "89") (name "unconnected-(U7-VCC-Pad23)") (class "Default")
      (node (ref "U7") (pin "23") (pinfunction "VCC_23") (pintype "passive"))
    )
  )
)
